# power_node.net
KiCad netlist of a schematic drawn in EAGLE
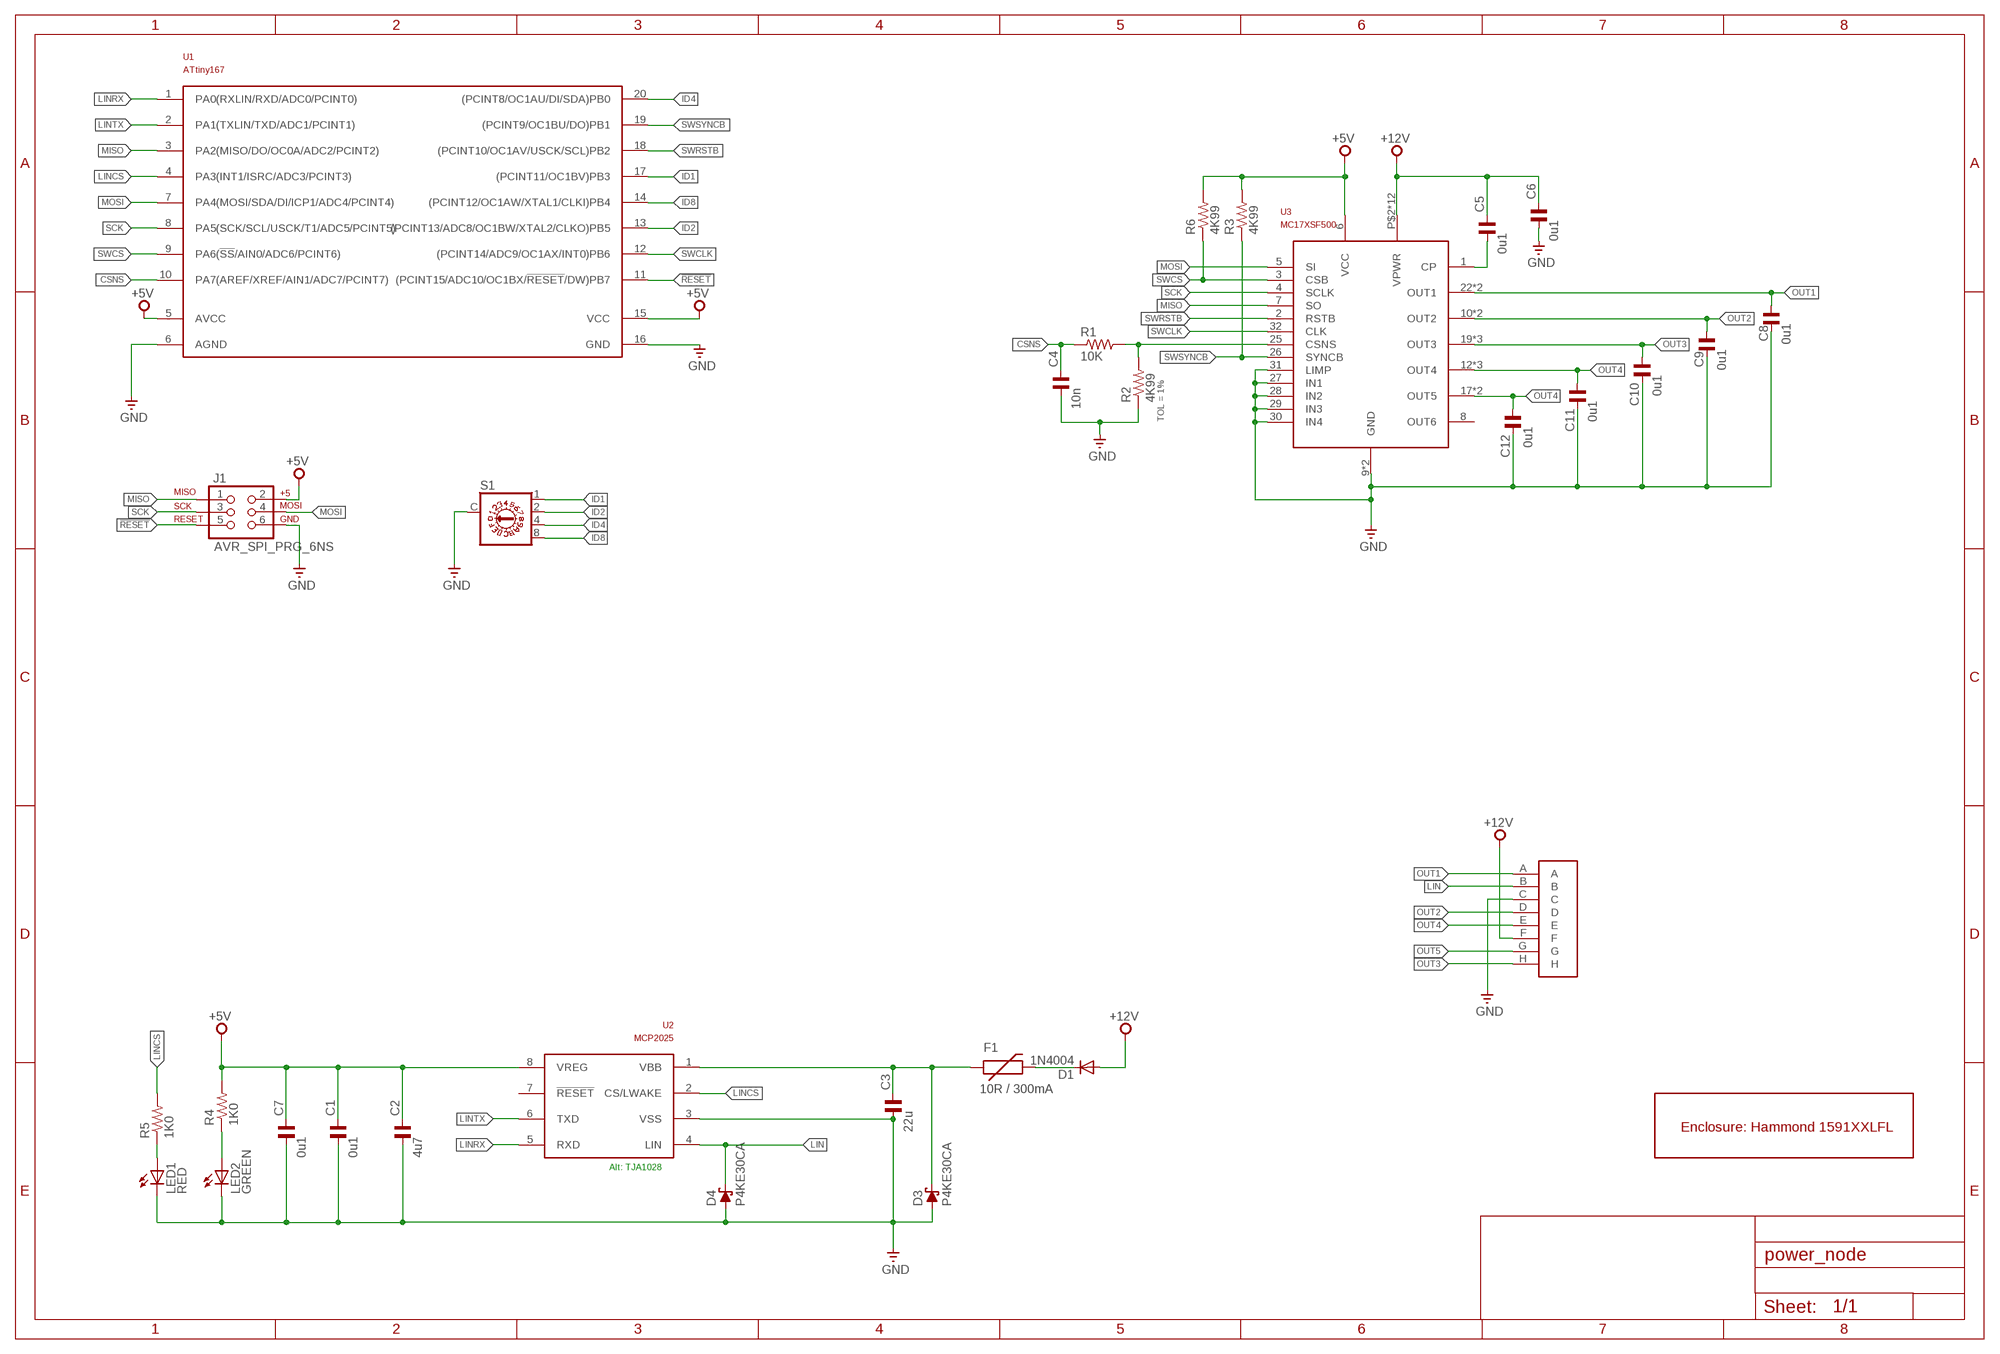
[diagram p0: schematic, sheet 1]

(export (version "E")
  (design (tool "Eeschema 10.0.6"))
  (components
    (comp (ref "C1")
      (value "0u1")
      (footprint "eagle-import:C050-024X044")
      (fields (field (name "PARTNO") "FK28X7R1H104K"))
      (libsource (lib "eagle-import") (part "C-EU050-024X044"))
    )
    (comp (ref "C2")
      (value "4u7")
      (footprint "eagle-import:C050-024X044")
      (fields (field (name "PARTNO") "FK28X5R0J475K"))
      (libsource (lib "eagle-import") (part "C-EU050-024X044"))
    )
    (comp (ref "C3")
      (value "22u")
      (footprint "eagle-import:C050-024X044")
      (fields (field (name "PARTNO") "FK22X5R1E226M"))
      (libsource (lib "eagle-import") (part "C-EU050-024X044"))
    )
    (comp (ref "C4")
      (value "10n")
      (footprint "eagle-import:C025-024X044")
      (fields (field (name "PARTNO") "FK18X7R1H103K"))
      (libsource (lib "eagle-import") (part "C-EU025-024X044"))
    )
    (comp (ref "C5")
      (value "0u1")
      (footprint "eagle-import:C050-024X044")
      (fields (field (name "PARTNO") "FK28X7R1H104K"))
      (libsource (lib "eagle-import") (part "C-EU050-024X044"))
    )
    (comp (ref "C6")
      (value "0u1")
      (footprint "eagle-import:C050-024X044")
      (fields (field (name "PARTNO") "FK28X7R1H104K"))
      (libsource (lib "eagle-import") (part "C-EU050-024X044"))
    )
    (comp (ref "C7")
      (value "0u1")
      (footprint "eagle-import:C050-024X044")
      (fields (field (name "PARTNO") "FK28X7R1H104K"))
      (libsource (lib "eagle-import") (part "C-EU050-024X044"))
    )
    (comp (ref "C8")
      (value "0u1")
      (footprint "eagle-import:C0603K")
      (fields (field (name "PARTNO") "C1608X7R1H104M080AA"))
      (libsource (lib "eagle-import") (part "C-EUC0603K"))
    )
    (comp (ref "C9")
      (value "0u1")
      (footprint "eagle-import:C0603K")
      (fields (field (name "PARTNO") "C1608X7R1H104M080AA"))
      (libsource (lib "eagle-import") (part "C-EUC0603K"))
    )
    (comp (ref "C10")
      (value "0u1")
      (footprint "eagle-import:C0603K")
      (fields (field (name "PARTNO") "C1608X7R1H104M080AA"))
      (libsource (lib "eagle-import") (part "C-EUC0603K"))
    )
    (comp (ref "C11")
      (value "0u1")
      (footprint "eagle-import:C0603K")
      (fields (field (name "PARTNO") "C1608X7R1H104M080AA"))
      (libsource (lib "eagle-import") (part "C-EUC0603K"))
    )
    (comp (ref "C12")
      (value "0u1")
      (footprint "eagle-import:C0603K")
      (fields (field (name "PARTNO") "C1608X7R1H104M080AA"))
      (libsource (lib "eagle-import") (part "C-EUC0603K"))
    )
    (comp (ref "D1")
      (value "1N4004")
      (footprint "eagle-import:DO41-10")
      (fields (field (name "PARTNO") "1N4004-TP"))
      (libsource (lib "eagle-import") (part "1N4004"))
    )
    (comp (ref "D3")
      (value "P4KE30CA")
      (footprint "eagle-import:DO41-10")
      (libsource (lib "eagle-import") (part "P4KEXX"))
    )
    (comp (ref "D4")
      (value "P4KE30CA")
      (footprint "eagle-import:DO41-10")
      (libsource (lib "eagle-import") (part "P4KEXX"))
    )
    (comp (ref "F1")
      (value "10R / 300mA")
      (footprint "eagle-import:PTC")
      (fields (field (name "PARTNO") "CMF-RL10-0"))
      (libsource (lib "eagle-import") (part "PTCPTH"))
    )
    (comp (ref "J1")
      (value "AVR_SPI_PRG_6NS")
      (footprint "eagle-import:2X3-NS")
      (libsource (lib "eagle-import") (part "AVR_SPI_PRG_6NS"))
    )
    (comp (ref "J2")
      (value "12146734")
      (footprint "eagle-import:12146734")
      (fields (field (name "PARTNO") "12146724-B"))
      (libsource (lib "eagle-import") (part "12146734"))
    )
    (comp (ref "LED1")
      (value "RED")
      (footprint "eagle-import:LED3MM")
      (fields (field (name "PARTNO") "C4SMF-RJS-CT0W0BB2"))
      (libsource (lib "eagle-import") (part "LED3MM"))
    )
    (comp (ref "LED2")
      (value "GREEN")
      (footprint "eagle-import:LED3MM")
      (fields (field (name "PARTNO") "C4SMF-GJS-CV0Y0792"))
      (libsource (lib "eagle-import") (part "LED3MM"))
    )
    (comp (ref "R1")
      (value "10K")
      (footprint "eagle-import:0207_10")
      (fields (field (name "PARTNO") "CF14JT10K0"))
      (libsource (lib "eagle-import") (part "R-EU_0207/10"))
    )
    (comp (ref "R2")
      (value "4K99")
      (footprint "eagle-import:0207_10")
      (fields (field (name "PARTNO") "MFR-25FBF52-4K99") (field (name "TOL") "1%"))
      (libsource (lib "eagle-import") (part "R-EU_0207/10"))
    )
    (comp (ref "R3")
      (value "4K99")
      (footprint "eagle-import:0207_10")
      (fields (field (name "PARTNO") "MFR-25FBF52-4K99"))
      (libsource (lib "eagle-import") (part "R-EU_0207/10"))
    )
    (comp (ref "R4")
      (value "1K0")
      (footprint "eagle-import:0207_10")
      (fields (field (name "PARTNO") "CF14JT1K00"))
      (libsource (lib "eagle-import") (part "R-EU_0207/10"))
    )
    (comp (ref "R5")
      (value "1K0")
      (footprint "eagle-import:0207_10")
      (fields (field (name "PARTNO") "CF14JT1K00"))
      (libsource (lib "eagle-import") (part "R-EU_0207/10"))
    )
    (comp (ref "R6")
      (value "4K99")
      (footprint "eagle-import:0207_10")
      (fields (field (name "PARTNO") "MFR-25FBF52-4K99"))
      (libsource (lib "eagle-import") (part "R-EU_0207/10"))
    )
    (comp (ref "S1")
      (value "P103")
      (footprint "eagle-import:P103")
      (fields (field (name "PARTNO") "SH-7050MC"))
      (libsource (lib "eagle-import") (part "P103"))
    )
    (comp (ref "U$1")
      (value "1591XXLFL")
      (footprint "eagle-import:1591XXLFL")
      (fields (field (name "PARTNO") "1591XXLFLBK"))
      (libsource (lib "eagle-import") (part "1591XXLFL"))
    )
    (comp (ref "U1")
      (value "ATtiny167")
      (footprint "eagle-import:SO20W")
      (fields (field (name "PARTNO") "ATTINY167-SU"))
      (libsource (lib "eagle-import") (part "ATTINY167"))
    )
    (comp (ref "U2")
      (value "MCP2025")
      (footprint "eagle-import:SO08")
      (fields (field (name "PARTNO") "MCP2025-500E/SN"))
      (libsource (lib "eagle-import") (part "MCP2025"))
    )
    (comp (ref "U3")
      (value "MC17XSF500")
      (footprint "eagle-import:SOIC32W-EP")
      (fields (field (name "PARTNO") "MC17XSF500EK"))
      (libsource (lib "eagle-import") (part "MC17XSF500"))
    )
  )
  (nets
    (net (code "1") (name "+5V") (class "Default")
      (node (ref "C1") (pin "1") (pinfunction "1_1") (pintype "passive"))
      (node (ref "C2") (pin "1") (pinfunction "1_1") (pintype "passive"))
      (node (ref "C7") (pin "1") (pinfunction "1_1") (pintype "passive"))
      (node (ref "J1") (pin "2") (pinfunction "2_2") (pintype "passive"))
      (node (ref "R3") (pin "2") (pinfunction "2_2") (pintype "passive"))
      (node (ref "R4") (pin "2") (pinfunction "2_2") (pintype "passive"))
      (node (ref "R6") (pin "2") (pinfunction "2_2") (pintype "passive"))
      (node (ref "U1") (pin "15") (pinfunction "VCC_15") (pintype "power_in"))
      (node (ref "U1") (pin "5") (pinfunction "AVCC_5") (pintype "power_in"))
      (node (ref "U2") (pin "8") (pinfunction "VREG_8") (pintype "power_in"))
      (node (ref "U3") (pin "6") (pinfunction "VCC_6") (pintype "power_in"))
    )
    (net (code "2") (name "+12V") (class "Default")
      (node (ref "C5") (pin "1") (pinfunction "1_1") (pintype "passive"))
      (node (ref "C6") (pin "1") (pinfunction "1_1") (pintype "passive"))
      (node (ref "D1") (pin "A") (pinfunction "A_A") (pintype "passive"))
      (node (ref "J2") (pin "F") (pinfunction "F_F") (pintype "bidirectional"))
      (node (ref "U3") (pin "P$10") (pinfunction "VPWR_P$10") (pintype "power_in"))
      (node (ref "U3") (pin "P$11") (pinfunction "VPWR_P$11") (pintype "power_in"))
      (node (ref "U3") (pin "P$12") (pinfunction "VPWR_P$12") (pintype "power_in"))
      (node (ref "U3") (pin "P$13") (pinfunction "VPWR_P$13") (pintype "power_in"))
      (node (ref "U3") (pin "P$2") (pinfunction "VPWR_P$2") (pintype "power_in"))
      (node (ref "U3") (pin "P$3") (pinfunction "VPWR_P$3") (pintype "power_in"))
      (node (ref "U3") (pin "P$4") (pinfunction "VPWR_P$4") (pintype "power_in"))
      (node (ref "U3") (pin "P$5") (pinfunction "VPWR_P$5") (pintype "power_in"))
      (node (ref "U3") (pin "P$6") (pinfunction "VPWR_P$6") (pintype "power_in"))
      (node (ref "U3") (pin "P$7") (pinfunction "VPWR_P$7") (pintype "power_in"))
      (node (ref "U3") (pin "P$8") (pinfunction "VPWR_P$8") (pintype "power_in"))
      (node (ref "U3") (pin "P$9") (pinfunction "VPWR_P$9") (pintype "power_in"))
    )
    (net (code "3") (name "/~{RESET}") (class "Default")
      (node (ref "J1") (pin "5") (pinfunction "5_5") (pintype "passive"))
      (node (ref "U1") (pin "11") (pinfunction "(PCINT15/ADC10/OC1BX/~{RESET}/DW)PB7_11") (pintype "bidirectional"))
    )
    (net (code "4") (name "CSNS") (class "Default")
      (node (ref "C4") (pin "1") (pinfunction "1_1") (pintype "passive"))
      (node (ref "R1") (pin "1") (pinfunction "1_1") (pintype "passive"))
      (node (ref "U1") (pin "10") (pinfunction "PA7(AREF/XREF/AIN1/ADC7/PCINT7)_10") (pintype "bidirectional"))
    )
    (net (code "5") (name "GND") (class "Default")
      (node (ref "C1") (pin "2") (pinfunction "2_2") (pintype "passive"))
      (node (ref "C10") (pin "2") (pinfunction "2_2") (pintype "passive"))
      (node (ref "C11") (pin "2") (pinfunction "2_2") (pintype "passive"))
      (node (ref "C12") (pin "2") (pinfunction "2_2") (pintype "passive"))
      (node (ref "C2") (pin "2") (pinfunction "2_2") (pintype "passive"))
      (node (ref "C3") (pin "2") (pinfunction "2_2") (pintype "passive"))
      (node (ref "C4") (pin "2") (pinfunction "2_2") (pintype "passive"))
      (node (ref "C6") (pin "2") (pinfunction "2_2") (pintype "passive"))
      (node (ref "C7") (pin "2") (pinfunction "2_2") (pintype "passive"))
      (node (ref "C8") (pin "2") (pinfunction "2_2") (pintype "passive"))
      (node (ref "C9") (pin "2") (pinfunction "2_2") (pintype "passive"))
      (node (ref "D3") (pin "A") (pinfunction "A_A") (pintype "passive"))
      (node (ref "D4") (pin "A") (pinfunction "A_A") (pintype "passive"))
      (node (ref "J1") (pin "6") (pinfunction "6_6") (pintype "passive"))
      (node (ref "J2") (pin "C") (pinfunction "C_C") (pintype "bidirectional"))
      (node (ref "LED1") (pin "K") (pinfunction "C_K") (pintype "passive"))
      (node (ref "LED2") (pin "K") (pinfunction "C_K") (pintype "passive"))
      (node (ref "R2") (pin "1") (pinfunction "1_1") (pintype "passive"))
      (node (ref "S1") (pin "C") (pinfunction "C_C") (pintype "passive"))
      (node (ref "U1") (pin "16") (pinfunction "GND_16") (pintype "power_in"))
      (node (ref "U1") (pin "6") (pinfunction "AGND_6") (pintype "power_in"))
      (node (ref "U2") (pin "3") (pinfunction "VSS_3") (pintype "power_in"))
      (node (ref "U3") (pin "24") (pinfunction "GND_24") (pintype "power_in"))
      (node (ref "U3") (pin "27") (pinfunction "IN1_27") (pintype "input"))
      (node (ref "U3") (pin "28") (pinfunction "IN2_28") (pintype "input"))
      (node (ref "U3") (pin "29") (pinfunction "IN3_29") (pintype "input"))
      (node (ref "U3") (pin "30") (pinfunction "IN4_30") (pintype "input"))
      (node (ref "U3") (pin "31") (pinfunction "LIMP_31") (pintype "input"))
      (node (ref "U3") (pin "9") (pinfunction "GND_9") (pintype "power_in"))
    )
    (net (code "6") (name "ID1") (class "Default")
      (node (ref "S1") (pin "1") (pinfunction "1_1") (pintype "passive"))
      (node (ref "U1") (pin "17") (pinfunction "(PCINT11/OC1BV)PB3_17") (pintype "bidirectional"))
    )
    (net (code "7") (name "ID2") (class "Default")
      (node (ref "S1") (pin "2") (pinfunction "2_2") (pintype "passive"))
      (node (ref "U1") (pin "13") (pinfunction "(PCINT13/ADC8/OC1BW/XTAL2/CLKO)PB5_13") (pintype "bidirectional"))
    )
    (net (code "8") (name "ID4") (class "Default")
      (node (ref "S1") (pin "4") (pinfunction "4_4") (pintype "passive"))
      (node (ref "U1") (pin "20") (pinfunction "(PCINT8/OC1AU/DI/SDA)PB0_20") (pintype "bidirectional"))
    )
    (net (code "9") (name "ID8") (class "Default")
      (node (ref "S1") (pin "8") (pinfunction "8_8") (pintype "passive"))
      (node (ref "U1") (pin "14") (pinfunction "(PCINT12/OC1AW/XTAL1/CLKI)PB4_14") (pintype "bidirectional"))
    )
    (net (code "10") (name "LIN") (class "Default")
      (node (ref "D4") (pin "C") (pinfunction "C_C") (pintype "passive"))
      (node (ref "J2") (pin "B") (pinfunction "B_B") (pintype "bidirectional"))
      (node (ref "U2") (pin "4") (pinfunction "LIN_4") (pintype "bidirectional"))
    )
    (net (code "11") (name "LINCS") (class "Default")
      (node (ref "R5") (pin "2") (pinfunction "2_2") (pintype "passive"))
      (node (ref "U1") (pin "4") (pinfunction "PA3(INT1/ISRC/ADC3/PCINT3)_4") (pintype "bidirectional"))
      (node (ref "U2") (pin "2") (pinfunction "CS/LWAKE_2") (pintype "input"))
    )
    (net (code "12") (name "LINRX") (class "Default")
      (node (ref "U1") (pin "1") (pinfunction "PA0(RXLIN/RXD/ADC0/PCINT0)_1") (pintype "bidirectional"))
      (node (ref "U2") (pin "5") (pinfunction "RXD_5") (pintype "output"))
    )
    (net (code "13") (name "LINTX") (class "Default")
      (node (ref "U1") (pin "2") (pinfunction "PA1(TXLIN/TXD/ADC1/PCINT1)_2") (pintype "bidirectional"))
      (node (ref "U2") (pin "6") (pinfunction "TXD_6") (pintype "input"))
    )
    (net (code "14") (name "MISO") (class "Default")
      (node (ref "J1") (pin "1") (pinfunction "1_1") (pintype "passive"))
      (node (ref "U1") (pin "3") (pinfunction "PA2(MISO/DO/OC0A/ADC2/PCINT2)_3") (pintype "bidirectional"))
      (node (ref "U3") (pin "7") (pinfunction "SO_7") (pintype "output"))
    )
    (net (code "15") (name "MOSI") (class "Default")
      (node (ref "J1") (pin "4") (pinfunction "4_4") (pintype "passive"))
      (node (ref "U1") (pin "7") (pinfunction "PA4(MOSI/SDA/DI/ICP1/ADC4/PCINT4)_7") (pintype "bidirectional"))
      (node (ref "U3") (pin "5") (pinfunction "SI_5") (pintype "input"))
    )
    (net (code "16") (name "Net-(F1-1)") (class "Default")
      (node (ref "C3") (pin "1") (pinfunction "1_1") (pintype "passive"))
      (node (ref "D3") (pin "C") (pinfunction "C_C") (pintype "passive"))
      (node (ref "F1") (pin "P$1") (pinfunction "1_P$1") (pintype "bidirectional"))
      (node (ref "U2") (pin "1") (pinfunction "VBB_1") (pintype "power_in"))
    )
    (net (code "17") (name "Net-(F1-2)") (class "Default")
      (node (ref "D1") (pin "C") (pinfunction "C_C") (pintype "passive"))
      (node (ref "F1") (pin "P$2") (pinfunction "2_P$2") (pintype "bidirectional"))
    )
    (net (code "18") (name "Net-(LED1-PadA)") (class "Default")
      (node (ref "LED1") (pin "A") (pinfunction "A_A") (pintype "passive"))
      (node (ref "R5") (pin "1") (pinfunction "1_1") (pintype "passive"))
    )
    (net (code "19") (name "Net-(LED2-PadA)") (class "Default")
      (node (ref "LED2") (pin "A") (pinfunction "A_A") (pintype "passive"))
      (node (ref "R4") (pin "1") (pinfunction "1_1") (pintype "passive"))
    )
    (net (code "20") (name "Net-(U3-CP)") (class "Default")
      (node (ref "C5") (pin "2") (pinfunction "2_2") (pintype "passive"))
      (node (ref "U3") (pin "1") (pinfunction "CP_1") (pintype "passive"))
    )
    (net (code "21") (name "Net-(U3-CSNS)") (class "Default")
      (node (ref "R1") (pin "2") (pinfunction "2_2") (pintype "passive"))
      (node (ref "R2") (pin "2") (pinfunction "2_2") (pintype "passive"))
      (node (ref "U3") (pin "25") (pinfunction "CSNS_25") (pintype "output"))
    )
    (net (code "22") (name "OUT1") (class "Default")
      (node (ref "C8") (pin "1") (pinfunction "1_1") (pintype "passive"))
      (node (ref "J2") (pin "A") (pinfunction "A_A") (pintype "bidirectional"))
      (node (ref "U3") (pin "22") (pinfunction "OUT1_22") (pintype "output"))
      (node (ref "U3") (pin "23") (pinfunction "OUT1_23") (pintype "output"))
    )
    (net (code "23") (name "OUT2") (class "Default")
      (node (ref "C9") (pin "1") (pinfunction "1_1") (pintype "passive"))
      (node (ref "J2") (pin "D") (pinfunction "D_D") (pintype "bidirectional"))
      (node (ref "U3") (pin "10") (pinfunction "OUT2_10") (pintype "output"))
      (node (ref "U3") (pin "11") (pinfunction "OUT2_11") (pintype "output"))
    )
    (net (code "24") (name "OUT3") (class "Default")
      (node (ref "C10") (pin "1") (pinfunction "1_1") (pintype "passive"))
      (node (ref "J2") (pin "H") (pinfunction "H_H") (pintype "bidirectional"))
      (node (ref "U3") (pin "19") (pinfunction "OUT3_19") (pintype "output"))
      (node (ref "U3") (pin "20") (pinfunction "OUT3_20") (pintype "output"))
      (node (ref "U3") (pin "21") (pinfunction "OUT3_21") (pintype "output"))
    )
    (net (code "25") (name "OUT4") (class "Default")
      (node (ref "C11") (pin "1") (pinfunction "1_1") (pintype "passive"))
      (node (ref "J2") (pin "E") (pinfunction "E_E") (pintype "bidirectional"))
      (node (ref "U3") (pin "12") (pinfunction "OUT4_12") (pintype "output"))
      (node (ref "U3") (pin "13") (pinfunction "OUT4_13") (pintype "output"))
      (node (ref "U3") (pin "14") (pinfunction "OUT4_14") (pintype "output"))
    )
    (net (code "26") (name "OUT5") (class "Default")
      (node (ref "C12") (pin "1") (pinfunction "1_1") (pintype "passive"))
      (node (ref "J2") (pin "G") (pinfunction "G_G") (pintype "bidirectional"))
      (node (ref "U3") (pin "17") (pinfunction "OUT5_17") (pintype "output"))
      (node (ref "U3") (pin "18") (pinfunction "OUT5_18") (pintype "output"))
    )
    (net (code "27") (name "SCK") (class "Default")
      (node (ref "J1") (pin "3") (pinfunction "3_3") (pintype "passive"))
      (node (ref "U1") (pin "8") (pinfunction "PA5(SCK/SCL/USCK/T1/ADC5/PCINT5)_8") (pintype "bidirectional"))
      (node (ref "U3") (pin "4") (pinfunction "SCLK_4") (pintype "input"))
    )
    (net (code "28") (name "SWCLK") (class "Default")
      (node (ref "U1") (pin "12") (pinfunction "(PCINT14/ADC9/OC1AX/INT0)PB6_12") (pintype "bidirectional"))
      (node (ref "U3") (pin "32") (pinfunction "CLK_32") (pintype "bidirectional"))
    )
    (net (code "29") (name "SWCS") (class "Default")
      (node (ref "R6") (pin "1") (pinfunction "1_1") (pintype "passive"))
      (node (ref "U1") (pin "9") (pinfunction "PA6(~{SS}/AIN0/ADC6/PCINT6)_9") (pintype "bidirectional"))
      (node (ref "U3") (pin "3") (pinfunction "CSB_3") (pintype "input"))
    )
    (net (code "30") (name "SWRSTB") (class "Default")
      (node (ref "U1") (pin "18") (pinfunction "(PCINT10/OC1AV/USCK/SCL)PB2_18") (pintype "bidirectional"))
      (node (ref "U3") (pin "2") (pinfunction "RSTB_2") (pintype "input"))
    )
    (net (code "31") (name "SWSYNCB") (class "Default")
      (node (ref "R3") (pin "1") (pinfunction "1_1") (pintype "passive"))
      (node (ref "U1") (pin "19") (pinfunction "(PCINT9/OC1BU/DO)PB1_19") (pintype "bidirectional"))
      (node (ref "U3") (pin "26") (pinfunction "SYNCB_26") (pintype "open_collector"))
    )
    (net (code "32") (name "unconnected-(U2-~{RESET}-Pad7)") (class "Default")
      (node (ref "U2") (pin "7") (pinfunction "~{RESET}_7") (pintype "open_collector"))
    )
    (net (code "33") (name "unconnected-(U3-OUT6-Pad8)") (class "Default")
      (node (ref "U3") (pin "8") (pinfunction "OUT6_8") (pintype "output"))
    )
  )
)
